# Digital_Input.net
KiCad netlist of a schematic drawn in Altium Designer
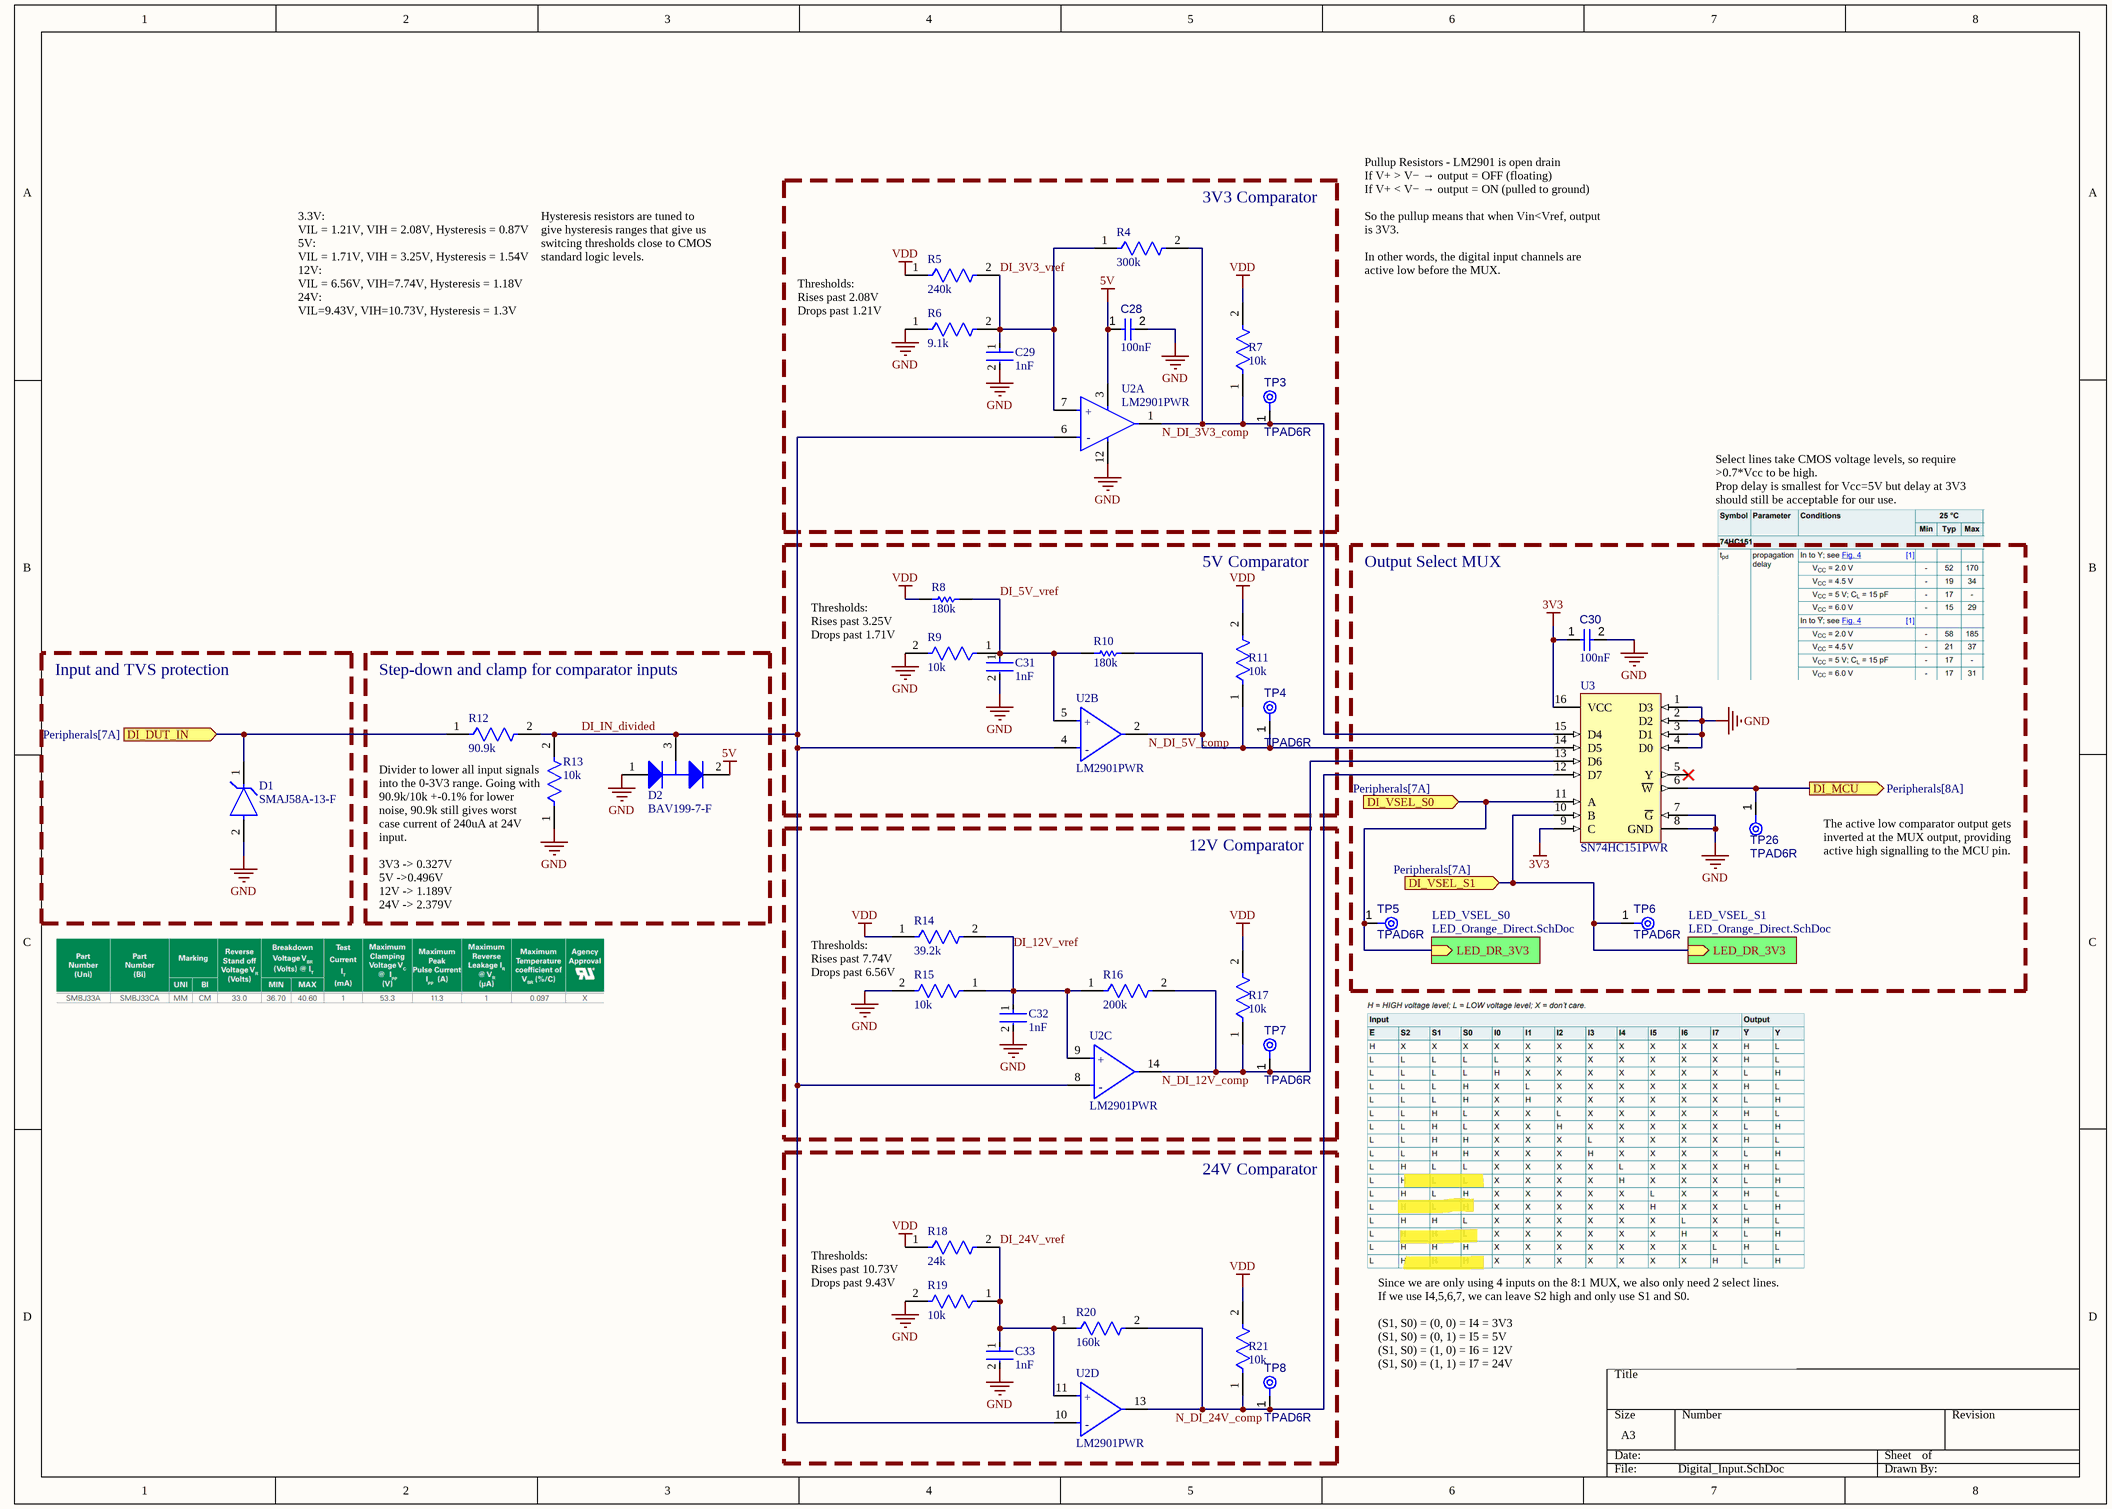
[diagram p0:  Digital_Input.SchDoc]

(export (version "E")
  (design (tool "Eeschema 10.0.6"))
  (components
    (comp (ref "C28")
      (value "100nF")
      (footprint "CAPC1608X90X40NL10T20")
      (description "Chip Capacitor, 100 nF, +/- 10%, 50 V, 0603 (1608 Metric)")
      (fields (field (name "TOLERANCE") "10%") (field (name "Comment") "Capacitor 100 nF +/-10% 50 V 0603"))
      (libsource (lib "HIL RIG FYP") (part "CAP-NP-2"))
    )
    (comp (ref "C29")
      (value "1nF")
      (footprint "FP-CC0603-DA-IPC_B")
      (description "16V 1nF X7R ±10% 0603 Multilayer Ceramic Capacitors MLCC - SMD/SMT ROHS")
      (fields (field (name "TOLERANCE") "10%") (field (name "Comment") "CC0603KRX7R7BB102"))
      (libsource (lib "HIL RIG FYP") (part "11868f565c42a9108669ba33697ecf6"))
    )
    (comp (ref "C30")
      (value "100nF")
      (footprint "CAPC1608X90X40NL10T20")
      (description "Chip Capacitor, 100 nF, +/- 10%, 50 V, 0603 (1608 Metric)")
      (fields (field (name "TOLERANCE") "10%") (field (name "Comment") "Capacitor 100 nF +/-10% 50 V 0603"))
      (libsource (lib "HIL RIG FYP") (part "CAP-NP-2"))
    )
    (comp (ref "C31")
      (value "1nF")
      (footprint "FP-CC0603-DA-IPC_B")
      (description "16V 1nF X7R ±10% 0603 Multilayer Ceramic Capacitors MLCC - SMD/SMT ROHS")
      (fields (field (name "TOLERANCE") "10%") (field (name "Comment") "CC0603KRX7R7BB102"))
      (libsource (lib "HIL RIG FYP") (part "11868f565c42a9108669ba33697ecf6"))
    )
    (comp (ref "C32")
      (value "1nF")
      (footprint "FP-CC0603-DA-IPC_B")
      (description "16V 1nF X7R ±10% 0603 Multilayer Ceramic Capacitors MLCC - SMD/SMT ROHS")
      (fields (field (name "TOLERANCE") "10%") (field (name "Comment") "CC0603KRX7R7BB102"))
      (libsource (lib "HIL RIG FYP") (part "11868f565c42a9108669ba33697ecf6"))
    )
    (comp (ref "C33")
      (value "1nF")
      (footprint "FP-CC0603-DA-IPC_B")
      (description "16V 1nF X7R ±10% 0603 Multilayer Ceramic Capacitors MLCC - SMD/SMT ROHS")
      (fields (field (name "TOLERANCE") "10%") (field (name "Comment") "CC0603KRX7R7BB102"))
      (libsource (lib "HIL RIG FYP") (part "11868f565c42a9108669ba33697ecf6"))
    )
    (comp (ref "D1")
      (value "SMAJ58A-13-F")
      (footprint "FP-SMA-MFG")
      (description "SMAJ Series 58 V 400 W SMT Uni-Directional TVS Diode - DO-214AC")
      (libsource (lib "HIL RIG FYP") (part "f813f71cba58e380607f5dd3caf9714"))
    )
    (comp (ref "D2")
      (value "BAV199-7-F")
      (footprint "DIOD-SOT23-3_A_V")
      (description "Diode Standard Recovery Rectifier 85 Volt 0.16A 3-Pin SOT-23 Tape and Reel")
      (libsource (lib "HIL RIG FYP") (part "D-AKC-3"))
    )
    (comp (ref "R4")
      (value "300k")
      (footprint "FP-RT0603-IPC_C")
      (description "100mW Thin Film Resistor ±50ppm/℃ ±0.1% 300kΩ 0603 Chip Resistor - Surface Mount ROHS")
      (fields (field (name "TOLERANCE") "0.1%") (field (name "Comment") "RT0603BRE07300KL"))
      (libsource (lib "HIL RIG FYP") (part "1029c3af85768c4190bb7ad29bc67b5"))
    )
    (comp (ref "R5")
      (value "240k")
      (footprint "FP-RT0603-IPC_C")
      (description "Res Thin Film 0603 240K Ohm 0.1% 0.1W(1/10W) ±25ppm/C Pad SMD T/R")
      (fields (field (name "TOLERANCE") "0.1%") (field (name "Comment") "RT0603BRD07240KL"))
      (libsource (lib "HIL RIG FYP") (part "1029c3af85768c4190bb7ad29bc67b5"))
    )
    (comp (ref "R6")
      (value "9.1k")
      (footprint "FP-RT0603-IPC_C")
      (description "100mW Thin Film Resistor 75V ±25ppm/℃ ±0.1% 9.1kΩ 0603 Chip Resistor - Surface Mount ROHS")
      (fields (field (name "TOLERANCE") "0.1%") (field (name "Comment") "RT0603BRD079K1L"))
      (libsource (lib "HIL RIG FYP") (part "1029c3af85768c4190bb7ad29bc67b5"))
    )
    (comp (ref "R7")
      (value "10k")
      (footprint "FP-RT0603-IPC_C")
      (description "Res Thin Film 0603 10K Ohm 0.1% 1/10W ¦25ppm/¦C SMD Paper T/R")
      (fields (field (name "TOLERANCE") "0.1%") (field (name "Comment") "RT0603BRD0710KL"))
      (libsource (lib "HIL RIG FYP") (part "1029c3af85768c4190bb7ad29bc67b5"))
    )
    (comp (ref "R8")
      (value "180k")
      (footprint "RESC1608X55X30NL20T20")
      (description "Res Thin Film 0603 180K Ohm 0.1% 0.1W ±25ppm/°C Molded SMD Punched Carrier T/R")
      (fields (field (name "TOLERANCE") "0.1%") (field (name "Comment") "ERA-3AEB184V"))
      (libsource (lib "HIL RIG FYP") (part "RES"))
    )
    (comp (ref "R9")
      (value "10k")
      (footprint "FP-RT0603-IPC_C")
      (description "Res Thin Film 0603 10K Ohm 0.1% 1/10W ¦25ppm/¦C SMD Paper T/R")
      (fields (field (name "TOLERANCE") "0.1%") (field (name "Comment") "RT0603BRD0710KL"))
      (libsource (lib "HIL RIG FYP") (part "1029c3af85768c4190bb7ad29bc67b5"))
    )
    (comp (ref "R10")
      (value "180k")
      (footprint "RESC1608X55X30NL20T20")
      (description "Res Thin Film 0603 180K Ohm 0.1% 0.1W ±25ppm/°C Molded SMD Punched Carrier T/R")
      (fields (field (name "TOLERANCE") "0.1%") (field (name "Comment") "ERA-3AEB184V"))
      (libsource (lib "HIL RIG FYP") (part "RES"))
    )
    (comp (ref "R11")
      (value "10k")
      (footprint "FP-RT0603-IPC_C")
      (description "Res Thin Film 0603 10K Ohm 0.1% 1/10W ¦25ppm/¦C SMD Paper T/R")
      (fields (field (name "TOLERANCE") "0.1%") (field (name "Comment") "RT0603BRD0710KL"))
      (libsource (lib "HIL RIG FYP") (part "1029c3af85768c4190bb7ad29bc67b5"))
    )
    (comp (ref "R12")
      (value "90.9k")
      (footprint "FP-RT0603-IPC_C")
      (description "100mW Thin Film Resistor 75V ±25ppm/℃ ±0.1% 90.9kΩ 0603 Chip Resistor - Surface Mount ROHS")
      (fields (field (name "TOLERANCE") "0.1%") (field (name "Comment") "RT0603BRD0790K9L"))
      (libsource (lib "HIL RIG FYP") (part "1029c3af85768c4190bb7ad29bc67b5"))
    )
    (comp (ref "R13")
      (value "10k")
      (footprint "FP-RT0603-IPC_C")
      (description "Res Thin Film 0603 10K Ohm 0.1% 1/10W ¦25ppm/¦C SMD Paper T/R")
      (fields (field (name "TOLERANCE") "0.1%") (field (name "Comment") "RT0603BRD0710KL"))
      (libsource (lib "HIL RIG FYP") (part "1029c3af85768c4190bb7ad29bc67b5"))
    )
    (comp (ref "R14")
      (value "39.2k")
      (footprint "FP-RT0603-IPC_C")
      (description "100mW Thin Film Resistor ±25ppm/℃ ±0.1% 39.2kΩ 0603 Chip Resistor - Surface Mount ROHS")
      (fields (field (name "TOLERANCE") "0.1%") (field (name "Comment") "RT0603BRD0739K2L"))
      (libsource (lib "HIL RIG FYP") (part "1029c3af85768c4190bb7ad29bc67b5"))
    )
    (comp (ref "R15")
      (value "10k")
      (footprint "FP-RT0603-IPC_C")
      (description "Res Thin Film 0603 10K Ohm 0.1% 1/10W ¦25ppm/¦C SMD Paper T/R")
      (fields (field (name "TOLERANCE") "0.1%") (field (name "Comment") "RT0603BRD0710KL"))
      (libsource (lib "HIL RIG FYP") (part "1029c3af85768c4190bb7ad29bc67b5"))
    )
    (comp (ref "R16")
      (value "200k")
      (footprint "FP-AT0603-IPC_A")
      (description "100mW Thin Film Resistor ±25ppm/℃ ±0.1% 200kΩ 0603 Chip Resistor - Surface Mount ROHS")
      (fields (field (name "TOLERANCE") "0.1%") (field (name "Comment") "AT0603BRD07200KL"))
      (libsource (lib "HIL RIG FYP") (part "1029c3af85768c4190bb7ad29bc67b5"))
    )
    (comp (ref "R17")
      (value "10k")
      (footprint "FP-RT0603-IPC_C")
      (description "Res Thin Film 0603 10K Ohm 0.1% 1/10W ¦25ppm/¦C SMD Paper T/R")
      (fields (field (name "TOLERANCE") "0.1%") (field (name "Comment") "RT0603BRD0710KL"))
      (libsource (lib "HIL RIG FYP") (part "1029c3af85768c4190bb7ad29bc67b5"))
    )
    (comp (ref "R18")
      (value "24k")
      (footprint "FP-TNPW0603-e3-IPC_A")
      (description "Res Thin Film 0603 24K Ohm 0.1% 1/8W ±25ppm/°C Molded SMD SMD Paper T/R")
      (fields (field (name "TOLERANCE") "0.1%") (field (name "Comment") "TNPW060324K0BEEA"))
      (libsource (lib "HIL RIG FYP") (part "1029c3af85768c4190bb7ad29bc67b5"))
    )
    (comp (ref "R19")
      (value "10k")
      (footprint "FP-RT0603-IPC_C")
      (description "Res Thin Film 0603 10K Ohm 0.1% 1/10W ¦25ppm/¦C SMD Paper T/R")
      (fields (field (name "TOLERANCE") "0.1%") (field (name "Comment") "RT0603BRD0710KL"))
      (libsource (lib "HIL RIG FYP") (part "1029c3af85768c4190bb7ad29bc67b5"))
    )
    (comp (ref "R20")
      (value "160k")
      (footprint "FP-RT0603-IPC_C")
      (description "Res Thin Film 0603 160K Ohm 0.1% 0.1W(1/10W) ±25ppm/C Pad SMD T/R")
      (fields (field (name "TOLERANCE") "0.1%") (field (name "Comment") "RT0603BRD07160KL"))
      (libsource (lib "HIL RIG FYP") (part "1029c3af85768c4190bb7ad29bc67b5"))
    )
    (comp (ref "R21")
      (value "10k")
      (footprint "FP-RT0603-IPC_C")
      (description "Res Thin Film 0603 10K Ohm 0.1% 1/10W ¦25ppm/¦C SMD Paper T/R")
      (fields (field (name "TOLERANCE") "0.1%") (field (name "Comment") "RT0603BRD0710KL"))
      (libsource (lib "HIL RIG FYP") (part "1029c3af85768c4190bb7ad29bc67b5"))
    )
    (comp (ref "TP3")
      (value "TPAD6R")
      (footprint "TP06R")
      (description "0.6mm round")
      (libsource (lib "HIL RIG FYP") (part "CMP-001-0001-4"))
    )
    (comp (ref "TP4")
      (value "TPAD6R")
      (footprint "TP06R")
      (description "0.6mm round")
      (libsource (lib "HIL RIG FYP") (part "CMP-001-0001-4"))
    )
    (comp (ref "TP5")
      (value "TPAD6R")
      (footprint "TP06R")
      (description "0.6mm round")
      (libsource (lib "HIL RIG FYP") (part "CMP-001-0001-4"))
    )
    (comp (ref "TP6")
      (value "TPAD6R")
      (footprint "TP06R")
      (description "0.6mm round")
      (libsource (lib "HIL RIG FYP") (part "CMP-001-0001-4"))
    )
    (comp (ref "TP7")
      (value "TPAD6R")
      (footprint "TP06R")
      (description "0.6mm round")
      (libsource (lib "HIL RIG FYP") (part "CMP-001-0001-4"))
    )
    (comp (ref "TP8")
      (value "TPAD6R")
      (footprint "TP06R")
      (description "0.6mm round")
      (libsource (lib "HIL RIG FYP") (part "CMP-001-0001-4"))
    )
    (comp (ref "TP26")
      (value "TPAD6R")
      (footprint "TP06R")
      (description "0.6mm round")
      (libsource (lib "HIL RIG FYP") (part "CMP-001-0001-4"))
    )
    (comp (ref "U2")
      (value "LM2901PWR")
      (footprint "FP-PW0014A-IPC_B")
      (description "Cut Tape (CT) LM2901 CMOS MOS Open-Collector TTL 0.25muA comparator circuit 250nA 1.3mus 5mm 9V")
      (libsource (lib "HIL RIG FYP") (part "194f83ff06066585c623a61d885a339"))
    )
    (comp (ref "U3")
      (value "SN74HC151PWR")
      (footprint "PW0016A_L")
      (description "Multiplexer 1-ELEMENT Cmos 8-IN 16-PIN TSSOP T/r / IC Selector/mux 8-1LINE 16-TSSOP")
      (libsource (lib "HIL RIG FYP") (part "TI-SNX4XXX151-16"))
    )
  )
  (nets
    (net (code "1") (name "/DI_3V3_vref") (class "Default")
      (node (ref "C29") (pin "1") (pinfunction "1_1") (pintype "passive"))
      (node (ref "R4") (pin "1") (pinfunction "1_1") (pintype "passive"))
      (node (ref "R5") (pin "2") (pinfunction "2_2") (pintype "passive"))
      (node (ref "R6") (pin "2") (pinfunction "2_2") (pintype "passive"))
      (node (ref "U2") (pin "7") (pinfunction "1IN+_7") (pintype "tri_state"))
    )
    (net (code "2") (name "/DI_5V_vref") (class "Default")
      (node (ref "C31") (pin "1") (pinfunction "1_1") (pintype "passive"))
      (node (ref "R10") (pin "1") (pinfunction "1_1") (pintype "passive"))
      (node (ref "R8") (pin "2") (pinfunction "2_2") (pintype "passive"))
      (node (ref "R9") (pin "1") (pinfunction "1_1") (pintype "passive"))
      (node (ref "U2") (pin "5") (pinfunction "2IN+_5") (pintype "tri_state"))
    )
    (net (code "3") (name "/DI_12V_vref") (class "Default")
      (node (ref "C32") (pin "1") (pinfunction "1_1") (pintype "passive"))
      (node (ref "R14") (pin "2") (pinfunction "2_2") (pintype "passive"))
      (node (ref "R15") (pin "1") (pinfunction "1_1") (pintype "passive"))
      (node (ref "R16") (pin "1") (pinfunction "1_1") (pintype "passive"))
      (node (ref "U2") (pin "9") (pinfunction "3IN+_9") (pintype "tri_state"))
    )
    (net (code "4") (name "/DI_24V_vref") (class "Default")
      (node (ref "C33") (pin "1") (pinfunction "1_1") (pintype "passive"))
      (node (ref "R18") (pin "2") (pinfunction "2_2") (pintype "passive"))
      (node (ref "R19") (pin "1") (pinfunction "1_1") (pintype "passive"))
      (node (ref "R20") (pin "1") (pinfunction "1_1") (pintype "passive"))
      (node (ref "U2") (pin "11") (pinfunction "4IN+_11") (pintype "tri_state"))
    )
    (net (code "5") (name "/DI_DUT_IN") (class "Default")
      (node (ref "D1") (pin "1") (pinfunction "C_1") (pintype "passive"))
      (node (ref "R12") (pin "1") (pinfunction "1_1") (pintype "passive"))
    )
    (net (code "6") (name "/DI_IN_divided") (class "Default")
      (node (ref "D2") (pin "3") (pinfunction "C_3") (pintype "passive"))
      (node (ref "R12") (pin "2") (pinfunction "2_2") (pintype "passive"))
      (node (ref "R13") (pin "2") (pinfunction "2_2") (pintype "passive"))
      (node (ref "U2") (pin "10") (pinfunction "4IN-_10") (pintype "tri_state"))
      (node (ref "U2") (pin "4") (pinfunction "2IN-_4") (pintype "tri_state"))
      (node (ref "U2") (pin "6") (pinfunction "1IN-_6") (pintype "tri_state"))
      (node (ref "U2") (pin "8") (pinfunction "3IN-_8") (pintype "tri_state"))
    )
    (net (code "7") (name "/DI_MCU") (class "Default")
      (node (ref "TP26") (pin "1") (pinfunction "TP_1") (pintype "passive"))
      (node (ref "U3") (pin "6") (pinfunction "~{W}_6") (pintype "output"))
    )
    (net (code "8") (name "/DI_VSEL_S0") (class "Default")
      (node (ref "TP5") (pin "1") (pinfunction "TP_1") (pintype "passive"))
      (node (ref "U3") (pin "11") (pinfunction "A_11") (pintype "input"))
    )
    (net (code "9") (name "/DI_VSEL_S1") (class "Default")
      (node (ref "TP6") (pin "1") (pinfunction "TP_1") (pintype "passive"))
      (node (ref "U3") (pin "10") (pinfunction "B_10") (pintype "input"))
    )
    (net (code "10") (name "/N_DI_3V3_comp") (class "Default")
      (node (ref "R4") (pin "2") (pinfunction "2_2") (pintype "passive"))
      (node (ref "R7") (pin "1") (pinfunction "1_1") (pintype "passive"))
      (node (ref "TP3") (pin "1") (pinfunction "TP_1") (pintype "passive"))
      (node (ref "U2") (pin "1") (pinfunction "1OUT_1") (pintype "open_collector"))
      (node (ref "U3") (pin "15") (pinfunction "D4_15") (pintype "input"))
    )
    (net (code "11") (name "/N_DI_5V_comp") (class "Default")
      (node (ref "R10") (pin "2") (pinfunction "2_2") (pintype "passive"))
      (node (ref "R11") (pin "1") (pinfunction "1_1") (pintype "passive"))
      (node (ref "TP4") (pin "1") (pinfunction "TP_1") (pintype "passive"))
      (node (ref "U2") (pin "2") (pinfunction "2OUT_2") (pintype "open_collector"))
      (node (ref "U3") (pin "14") (pinfunction "D5_14") (pintype "input"))
    )
    (net (code "12") (name "/N_DI_12V_comp") (class "Default")
      (node (ref "R16") (pin "2") (pinfunction "2_2") (pintype "passive"))
      (node (ref "R17") (pin "1") (pinfunction "1_1") (pintype "passive"))
      (node (ref "TP7") (pin "1") (pinfunction "TP_1") (pintype "passive"))
      (node (ref "U2") (pin "14") (pinfunction "OUT3_14") (pintype "open_collector"))
      (node (ref "U3") (pin "13") (pinfunction "D6_13") (pintype "input"))
    )
    (net (code "13") (name "/N_DI_24V_comp") (class "Default")
      (node (ref "R20") (pin "2") (pinfunction "2_2") (pintype "passive"))
      (node (ref "R21") (pin "1") (pinfunction "1_1") (pintype "passive"))
      (node (ref "TP8") (pin "1") (pinfunction "TP_1") (pintype "passive"))
      (node (ref "U2") (pin "13") (pinfunction "OUT4_13") (pintype "open_collector"))
      (node (ref "U3") (pin "12") (pinfunction "D7_12") (pintype "input"))
    )
    (net (code "14") (name "3V3") (class "Default")
      (node (ref "C30") (pin "1") (pinfunction "1_1") (pintype "passive"))
      (node (ref "U3") (pin "16") (pinfunction "VCC_16") (pintype "power_in"))
      (node (ref "U3") (pin "9") (pinfunction "C_9") (pintype "input"))
    )
    (net (code "15") (name "5V") (class "Default")
      (node (ref "C28") (pin "1") (pinfunction "1_1") (pintype "passive"))
      (node (ref "D2") (pin "2") (pinfunction "K_2") (pintype "passive"))
      (node (ref "U2") (pin "3") (pinfunction "VCC_3") (pintype "power_in"))
    )
    (net (code "16") (name "GND") (class "Default")
      (node (ref "C28") (pin "2") (pinfunction "2_2") (pintype "passive"))
      (node (ref "C29") (pin "2") (pinfunction "2_2") (pintype "passive"))
      (node (ref "C30") (pin "2") (pinfunction "2_2") (pintype "passive"))
      (node (ref "C31") (pin "2") (pinfunction "2_2") (pintype "passive"))
      (node (ref "C32") (pin "2") (pinfunction "2_2") (pintype "passive"))
      (node (ref "C33") (pin "2") (pinfunction "2_2") (pintype "passive"))
      (node (ref "D1") (pin "2") (pinfunction "A_2") (pintype "passive"))
      (node (ref "D2") (pin "1") (pinfunction "A_1") (pintype "passive"))
      (node (ref "R13") (pin "1") (pinfunction "1_1") (pintype "passive"))
      (node (ref "R15") (pin "2") (pinfunction "2_2") (pintype "passive"))
      (node (ref "R19") (pin "2") (pinfunction "2_2") (pintype "passive"))
      (node (ref "R6") (pin "1") (pinfunction "1_1") (pintype "passive"))
      (node (ref "R9") (pin "2") (pinfunction "2_2") (pintype "passive"))
      (node (ref "U2") (pin "12") (pinfunction "GND_12") (pintype "power_in"))
      (node (ref "U3") (pin "1") (pinfunction "D3_1") (pintype "input"))
      (node (ref "U3") (pin "2") (pinfunction "D2_2") (pintype "input"))
      (node (ref "U3") (pin "3") (pinfunction "D1_3") (pintype "input"))
      (node (ref "U3") (pin "4") (pinfunction "D0_4") (pintype "input"))
      (node (ref "U3") (pin "7") (pinfunction "~{G}_7") (pintype "input"))
      (node (ref "U3") (pin "8") (pinfunction "GND_8") (pintype "power_in"))
    )
    (net (code "17") (name "VDD") (class "Default")
      (node (ref "R11") (pin "2") (pinfunction "2_2") (pintype "passive"))
      (node (ref "R14") (pin "1") (pinfunction "1_1") (pintype "passive"))
      (node (ref "R17") (pin "2") (pinfunction "2_2") (pintype "passive"))
      (node (ref "R18") (pin "1") (pinfunction "1_1") (pintype "passive"))
      (node (ref "R21") (pin "2") (pinfunction "2_2") (pintype "passive"))
      (node (ref "R5") (pin "1") (pinfunction "1_1") (pintype "passive"))
      (node (ref "R7") (pin "2") (pinfunction "2_2") (pintype "passive"))
      (node (ref "R8") (pin "1") (pinfunction "1_1") (pintype "passive"))
    )
    (net (code "18") (name "unconnected-(U3-Y-Pad5)") (class "Default")
      (node (ref "U3") (pin "5") (pinfunction "Y_5") (pintype "output+no_connect"))
    )
  )
)
